# FlightControl.net
KiCad netlist of a schematic drawn in EAGLE
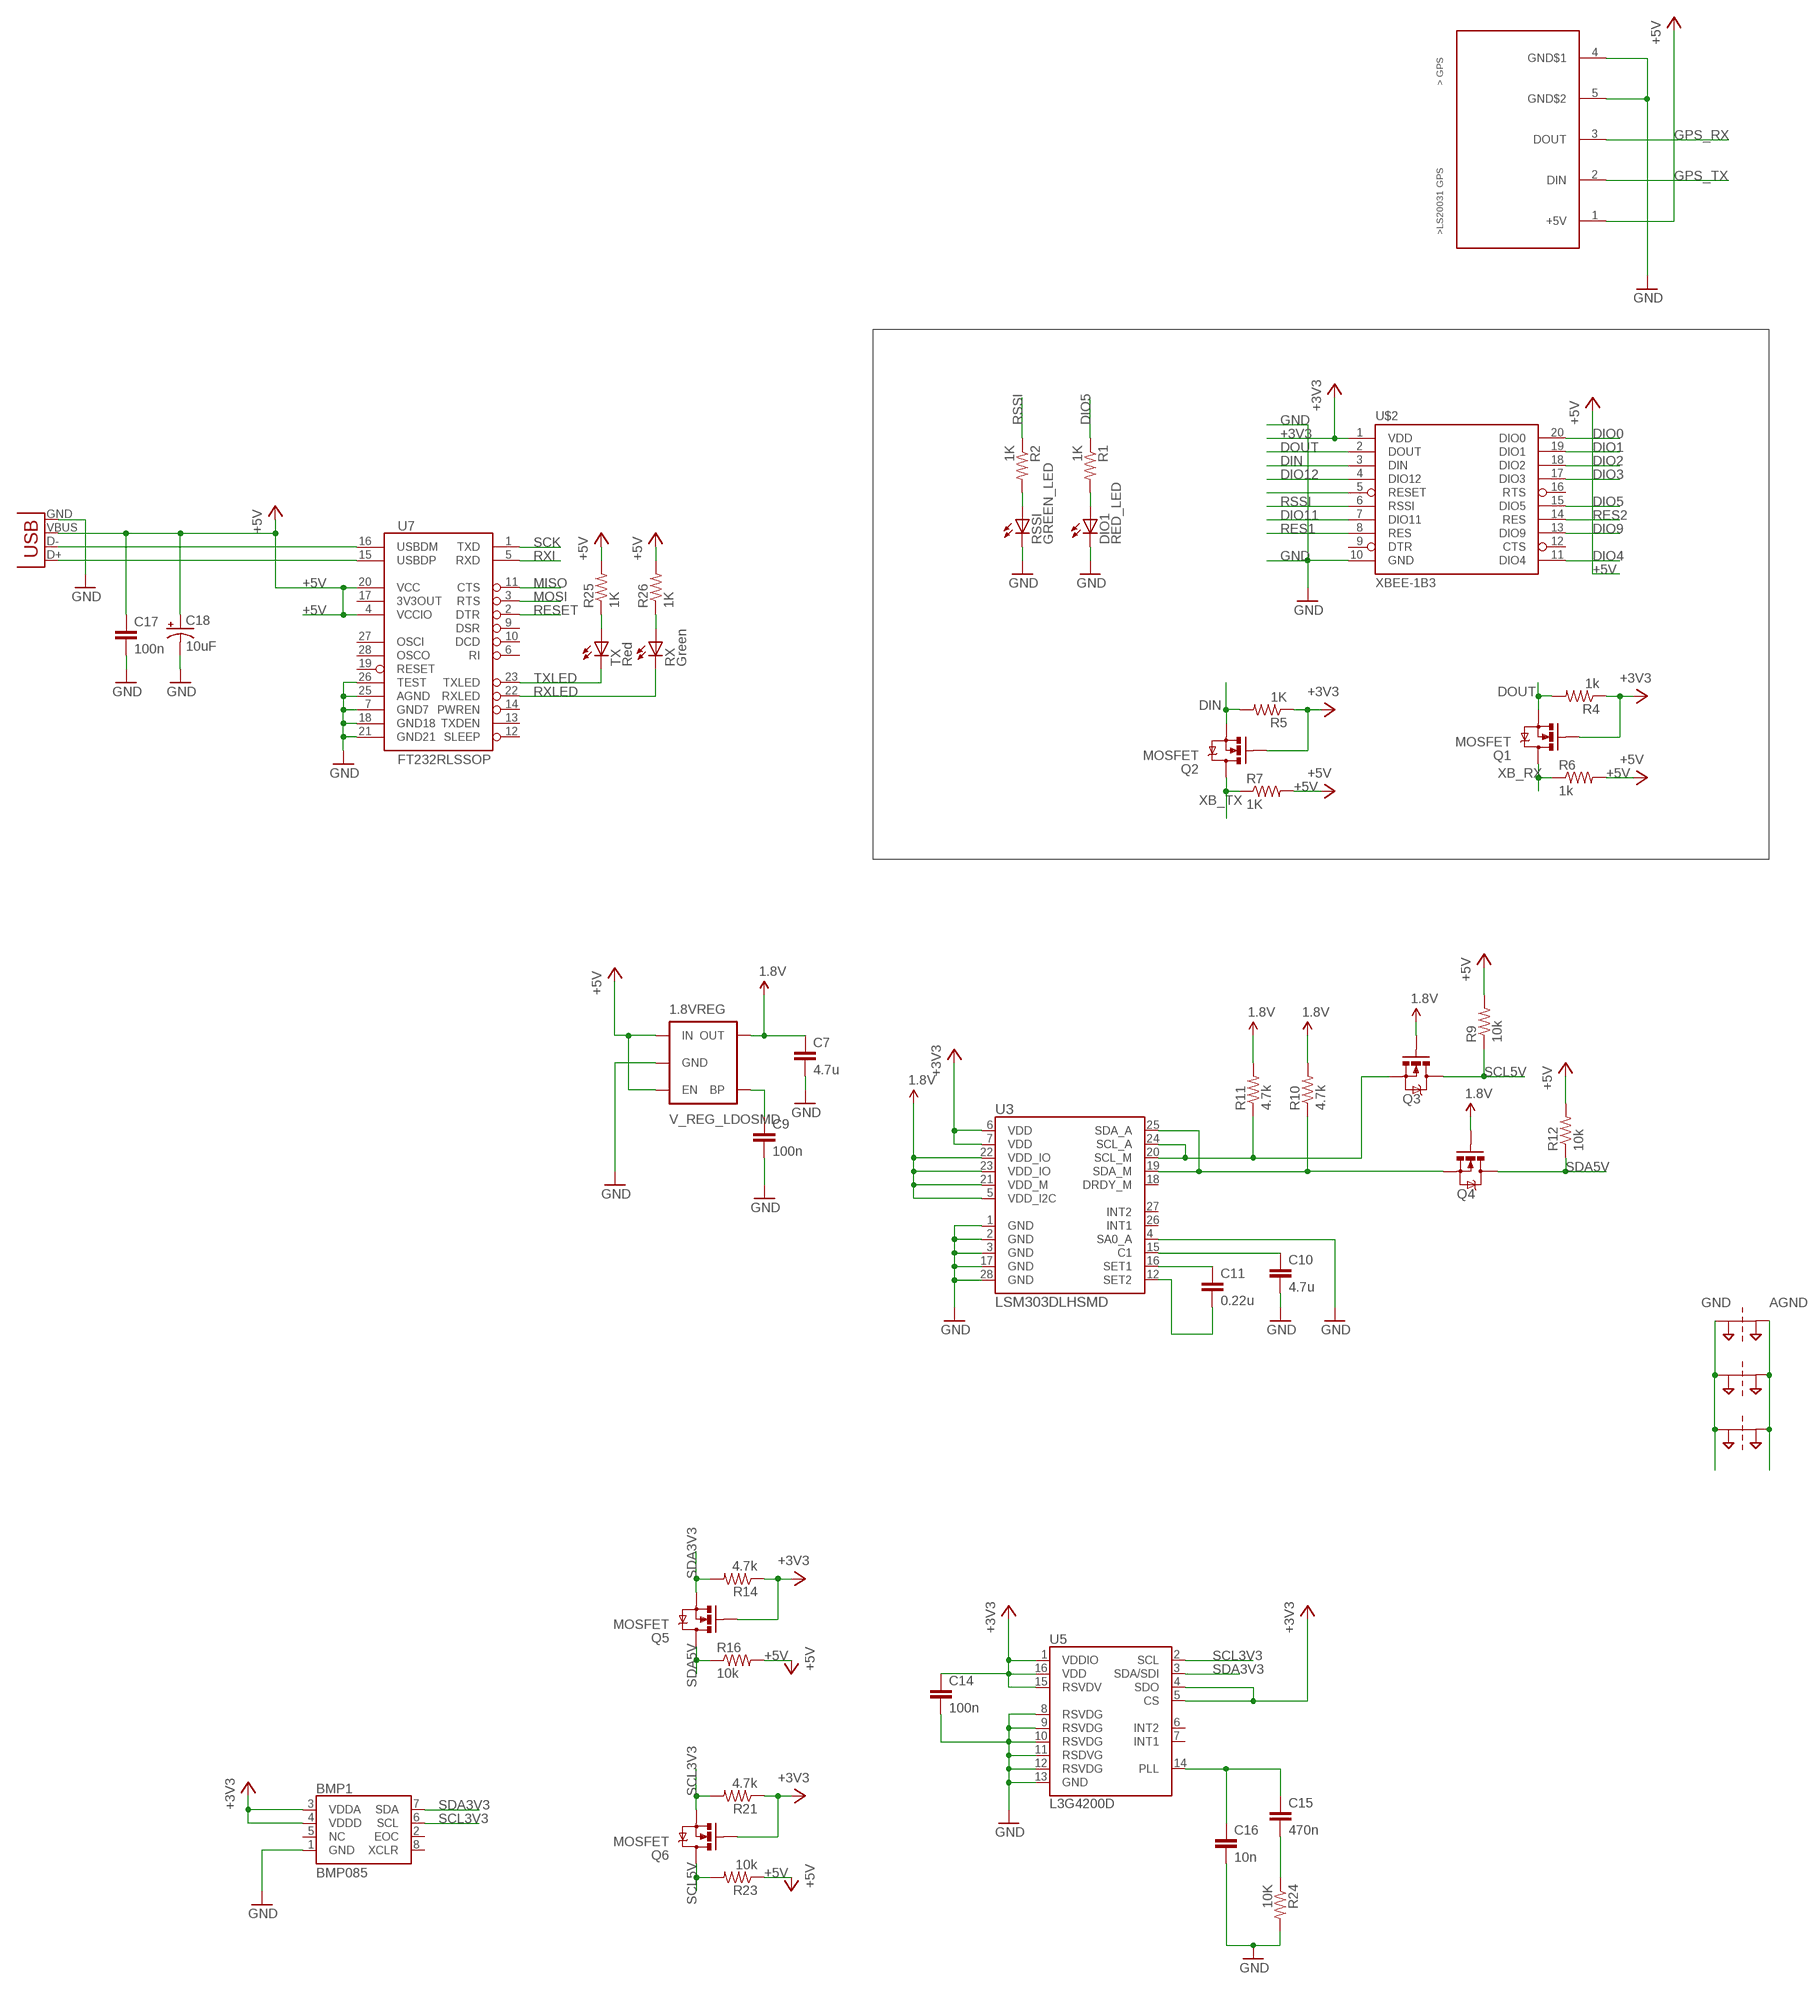
[diagram p0: schematic, sheet 1, part 1 of 2]
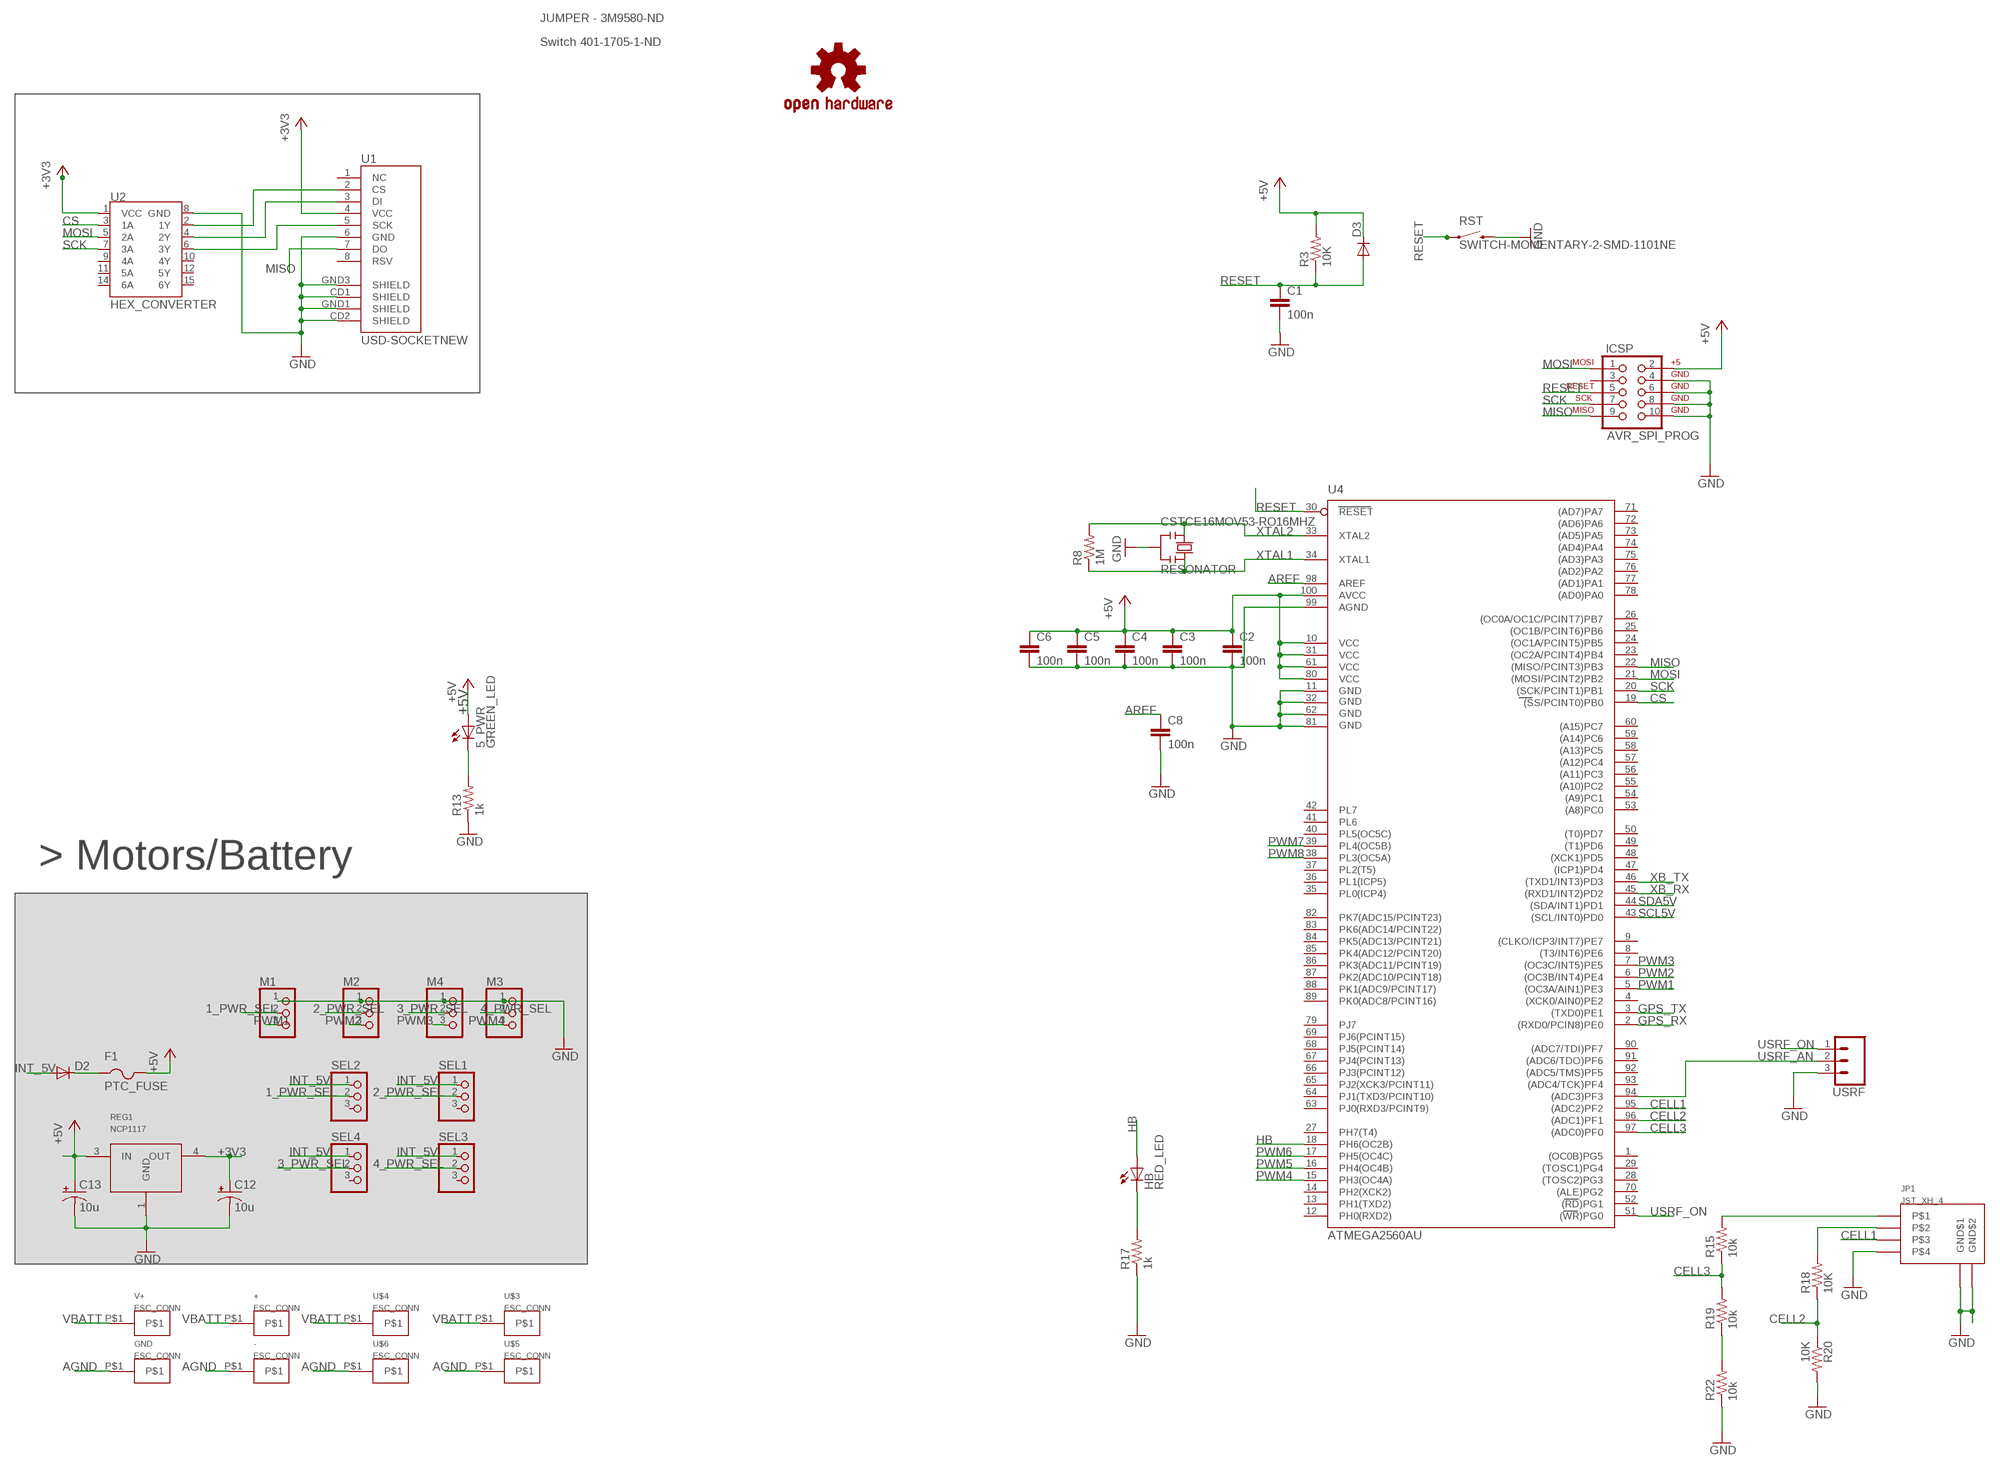
[diagram p1: schematic, sheet 1, part 2 of 2]

(export (version "E")
  (design (tool "Eeschema 10.0.6"))
  (components
    (comp (ref "+")
      (value "ESC_CONN")
      (footprint "eagle-import:ESC_CONN")
      (libsource (lib "eagle-import") (part "ESC_CONN"))
    )
    (comp (ref "-")
      (value "ESC_CONN")
      (footprint "eagle-import:ESC_CONN")
      (libsource (lib "eagle-import") (part "ESC_CONN"))
    )
    (comp (ref "1.8VREG")
      (value "V_REG_LDOSMD")
      (footprint "eagle-import:SOT23-5")
      (libsource (lib "eagle-import") (part "V_REG_LDOSMD"))
    )
    (comp (ref "5_PWR")
      (value "GREEN_LED")
      (footprint "eagle-import:LED-0603")
      (libsource (lib "eagle-import") (part "SparkFun-LED_LED0603"))
    )
    (comp (ref "BMP1")
      (value "BMP085")
      (footprint "eagle-import:BMP085")
      (libsource (lib "eagle-import") (part "BMP085"))
    )
    (comp (ref "C1")
      (value "100n")
      (footprint "eagle-import:0402-CAP")
      (libsource (lib "eagle-import") (part "SparkFun-Passives_CAP0402-CAP"))
    )
    (comp (ref "C2")
      (value "100n")
      (footprint "eagle-import:0402-CAP")
      (libsource (lib "eagle-import") (part "SparkFun-Passives_CAP0402-CAP"))
    )
    (comp (ref "C3")
      (value "100n")
      (footprint "eagle-import:0402-CAP")
      (libsource (lib "eagle-import") (part "SparkFun-Passives_CAP0402-CAP"))
    )
    (comp (ref "C4")
      (value "100n")
      (footprint "eagle-import:0402-CAP")
      (libsource (lib "eagle-import") (part "SparkFun-Passives_CAP0402-CAP"))
    )
    (comp (ref "C5")
      (value "100n")
      (footprint "eagle-import:0402-CAP")
      (libsource (lib "eagle-import") (part "SparkFun-Passives_CAP0402-CAP"))
    )
    (comp (ref "C6")
      (value "100n")
      (footprint "eagle-import:0402-CAP")
      (libsource (lib "eagle-import") (part "SparkFun-Passives_CAP0402-CAP"))
    )
    (comp (ref "C7")
      (value "4.7u")
      (footprint "eagle-import:0402-CAP")
      (libsource (lib "eagle-import") (part "SparkFun-Passives_CAP0402-CAP"))
    )
    (comp (ref "C8")
      (value "100n")
      (footprint "eagle-import:0402-CAP")
      (libsource (lib "eagle-import") (part "SparkFun-Passives_CAP0402-CAP"))
    )
    (comp (ref "C9")
      (value "100n")
      (footprint "eagle-import:0402-CAP")
      (libsource (lib "eagle-import") (part "SparkFun-Passives_CAP0402-CAP"))
    )
    (comp (ref "C10")
      (value "4.7u")
      (footprint "eagle-import:0402-CAP")
      (libsource (lib "eagle-import") (part "SparkFun-Passives_CAP0402-CAP"))
    )
    (comp (ref "C11")
      (value "0.22u")
      (footprint "eagle-import:0402-CAP")
      (libsource (lib "eagle-import") (part "SparkFun-Passives_CAP0402-CAP"))
    )
    (comp (ref "C12")
      (value "10u")
      (footprint "eagle-import:EIA3216")
      (libsource (lib "eagle-import") (part "SparkFun-Capacitors_CAP_POL1206"))
    )
    (comp (ref "C13")
      (value "10u")
      (footprint "eagle-import:EIA3216")
      (libsource (lib "eagle-import") (part "SparkFun-Capacitors_CAP_POL1206"))
    )
    (comp (ref "C14")
      (value "100n")
      (footprint "eagle-import:0402-CAP")
      (libsource (lib "eagle-import") (part "SparkFun-Capacitors_CAP0402-CAP"))
    )
    (comp (ref "C15")
      (value "470n")
      (footprint "eagle-import:0402-CAP")
      (libsource (lib "eagle-import") (part "SparkFun-Passives_CAP0402-CAP"))
    )
    (comp (ref "C16")
      (value "10n")
      (footprint "eagle-import:0402-CAP")
      (libsource (lib "eagle-import") (part "SparkFun-Passives_CAP0402-CAP"))
    )
    (comp (ref "C17")
      (value "100n")
      (footprint "eagle-import:0402-CAP")
      (libsource (lib "eagle-import") (part "CAP0402-CAP"))
    )
    (comp (ref "C18")
      (value "10uF")
      (footprint "eagle-import:EIA3216")
      (libsource (lib "eagle-import") (part "CAP_POL1206"))
    )
    (comp (ref "CSTCE16MOV53-RO16MHZ")
      (value "RESONATOR")
      (footprint "eagle-import:RESONATOR")
      (libsource (lib "eagle-import") (part "RESONATORMU"))
    )
    (comp (ref "D2")
      (value "SCHOTTKY-1206D1206")
      (footprint "eagle-import:C1206")
      (libsource (lib "eagle-import") (part "SCHOTTKY-1206D1206"))
    )
    (comp (ref "D3")
      (value "SCHOTTKY-1206D1206")
      (footprint "eagle-import:C1206")
      (libsource (lib "eagle-import") (part "SCHOTTKY-1206D1206"))
    )
    (comp (ref "DIO1")
      (value "RED_LED")
      (footprint "eagle-import:LED-0603")
      (libsource (lib "eagle-import") (part "SparkFun-LED_LED0603"))
    )
    (comp (ref "F1")
      (value "PTC_FUSE")
      (footprint "eagle-import:1812")
      (libsource (lib "eagle-import") (part "PTCFUSE-1812"))
    )
    (comp (ref "GND")
      (value "ESC_CONN")
      (footprint "eagle-import:ESC_CONN")
      (libsource (lib "eagle-import") (part "ESC_CONN"))
    )
    (comp (ref "HB")
      (value "RED_LED")
      (footprint "eagle-import:LED-0603")
      (libsource (lib "eagle-import") (part "SparkFun-LED_LED0603"))
    )
    (comp (ref "ICSP")
      (value "AVR_SPI_PROG")
      (footprint "eagle-import:AVR_ICSP")
      (libsource (lib "eagle-import") (part "AVR_SPI_PROG"))
    )
    (comp (ref "JP1")
      (value "JST_XH_4")
      (footprint "eagle-import:JST-XH4")
      (libsource (lib "eagle-import") (part "JST_XH_4"))
    )
    (comp (ref "LOGO1")
      (value "OSHW-LOGOL")
      (footprint "eagle-import:OSHW-LOGO-L")
      (libsource (lib "eagle-import") (part "OSHW-LOGOL"))
    )
    (comp (ref "M1")
      (value "PINHD-1X3")
      (footprint "eagle-import:1X03")
      (libsource (lib "eagle-import") (part "PINHD-1X3"))
    )
    (comp (ref "M2")
      (value "PINHD-1X3")
      (footprint "eagle-import:1X03")
      (libsource (lib "eagle-import") (part "PINHD-1X3"))
    )
    (comp (ref "M3")
      (value "PINHD-1X3")
      (footprint "eagle-import:1X03")
      (libsource (lib "eagle-import") (part "PINHD-1X3"))
    )
    (comp (ref "M4")
      (value "PINHD-1X3")
      (footprint "eagle-import:1X03")
      (libsource (lib "eagle-import") (part "PINHD-1X3"))
    )
    (comp (ref "PT1")
      (value "2PT_GND_TIE")
      (footprint "eagle-import:2PT_GND_TIE")
      (libsource (lib "eagle-import") (part "2PT_GND_TIE"))
    )
    (comp (ref "PT2")
      (value "2PT_GND_TIE")
      (footprint "eagle-import:2PT_GND_TIE")
      (libsource (lib "eagle-import") (part "2PT_GND_TIE"))
    )
    (comp (ref "PT3")
      (value "2PT_GND_TIE")
      (footprint "eagle-import:2PT_GND_TIE")
      (libsource (lib "eagle-import") (part "2PT_GND_TIE"))
    )
    (comp (ref "Q1")
      (value "MOSFET")
      (footprint "eagle-import:SOT23")
      (libsource (lib "eagle-import") (part "MOSFET-NCHANNELBSS138"))
    )
    (comp (ref "Q2")
      (value "MOSFET")
      (footprint "eagle-import:SOT23")
      (libsource (lib "eagle-import") (part "MOSFET-NCHANNELBSS138"))
    )
    (comp (ref "Q3")
      (value "MOSFET")
      (footprint "eagle-import:SOT23")
      (libsource (lib "eagle-import") (part "MOSFET-NCHANNELBSS138"))
    )
    (comp (ref "Q4")
      (value "MOSFET")
      (footprint "eagle-import:SOT23")
      (libsource (lib "eagle-import") (part "MOSFET-NCHANNELBSS138"))
    )
    (comp (ref "Q5")
      (value "MOSFET")
      (footprint "eagle-import:SOT23")
      (libsource (lib "eagle-import") (part "MOSFET-NCHANNELBSS138"))
    )
    (comp (ref "Q6")
      (value "MOSFET")
      (footprint "eagle-import:SOT23")
      (libsource (lib "eagle-import") (part "MOSFET-NCHANNELBSS138"))
    )
    (comp (ref "R1")
      (value "1K")
      (footprint "eagle-import:0603-RES")
      (libsource (lib "eagle-import") (part "RESISTOR0603-RES"))
    )
    (comp (ref "R2")
      (value "1K")
      (footprint "eagle-import:0603-RES")
      (libsource (lib "eagle-import") (part "RESISTOR0603-RES"))
    )
    (comp (ref "R3")
      (value "10K")
      (footprint "eagle-import:0603-RES")
      (libsource (lib "eagle-import") (part "RESISTOR0603-RES"))
    )
    (comp (ref "R4")
      (value "1k")
      (footprint "eagle-import:0603-RES")
      (libsource (lib "eagle-import") (part "RESISTOR0603-RES"))
    )
    (comp (ref "R5")
      (value "1K")
      (footprint "eagle-import:0603-RES")
      (libsource (lib "eagle-import") (part "RESISTOR0603-RES"))
    )
    (comp (ref "R6")
      (value "1k")
      (footprint "eagle-import:0603-RES")
      (libsource (lib "eagle-import") (part "RESISTOR0603-RES"))
    )
    (comp (ref "R7")
      (value "1K")
      (footprint "eagle-import:0603-RES")
      (libsource (lib "eagle-import") (part "RESISTOR0603-RES"))
    )
    (comp (ref "R8")
      (value "1M")
      (footprint "eagle-import:0603-RES")
      (libsource (lib "eagle-import") (part "RESISTOR0603-RES"))
    )
    (comp (ref "R9")
      (value "10k")
      (footprint "eagle-import:0603-RES")
      (libsource (lib "eagle-import") (part "RESISTOR0603-RES"))
    )
    (comp (ref "R10")
      (value "4.7k")
      (footprint "eagle-import:0402-RES")
      (libsource (lib "eagle-import") (part "RESISTOR0402-RES"))
    )
    (comp (ref "R11")
      (value "4.7k")
      (footprint "eagle-import:0603-RES")
      (libsource (lib "eagle-import") (part "RESISTOR0603-RES"))
    )
    (comp (ref "R12")
      (value "10k")
      (footprint "eagle-import:0603-RES")
      (libsource (lib "eagle-import") (part "RESISTOR0603-RES"))
    )
    (comp (ref "R13")
      (value "1k")
      (footprint "eagle-import:0603-RES")
      (libsource (lib "eagle-import") (part "RESISTOR0603-RES"))
    )
    (comp (ref "R14")
      (value "4.7k")
      (footprint "eagle-import:0603-RES")
      (libsource (lib "eagle-import") (part "RESISTOR0603-RES"))
    )
    (comp (ref "R15")
      (value "10k")
      (footprint "eagle-import:0603-RES")
      (libsource (lib "eagle-import") (part "RESISTOR0603-RES"))
    )
    (comp (ref "R16")
      (value "10k")
      (footprint "eagle-import:0603-RES")
      (libsource (lib "eagle-import") (part "RESISTOR0603-RES"))
    )
    (comp (ref "R17")
      (value "1k")
      (footprint "eagle-import:0603-RES")
      (libsource (lib "eagle-import") (part "RESISTOR0603-RES"))
    )
    (comp (ref "R18")
      (value "10K")
      (footprint "eagle-import:0603-RES")
      (libsource (lib "eagle-import") (part "RESISTOR0603-RES"))
    )
    (comp (ref "R19")
      (value "10k")
      (footprint "eagle-import:0603-RES")
      (libsource (lib "eagle-import") (part "RESISTOR0603-RES"))
    )
    (comp (ref "R20")
      (value "10K")
      (footprint "eagle-import:0603-RES")
      (libsource (lib "eagle-import") (part "RESISTOR0603-RES"))
    )
    (comp (ref "R21")
      (value "4.7k")
      (footprint "eagle-import:0603-RES")
      (libsource (lib "eagle-import") (part "RESISTOR0603-RES"))
    )
    (comp (ref "R22")
      (value "10k")
      (footprint "eagle-import:0603-RES")
      (libsource (lib "eagle-import") (part "RESISTOR0603-RES"))
    )
    (comp (ref "R23")
      (value "10k")
      (footprint "eagle-import:0603-RES")
      (libsource (lib "eagle-import") (part "RESISTOR0603-RES"))
    )
    (comp (ref "R24")
      (value "10K")
      (footprint "eagle-import:0603-RES")
      (libsource (lib "eagle-import") (part "RESISTOR0603-RES"))
    )
    (comp (ref "R25")
      (value "1K")
      (footprint "eagle-import:0603-RES")
      (libsource (lib "eagle-import") (part "RESISTOR0603-RES"))
    )
    (comp (ref "R26")
      (value "1K")
      (footprint "eagle-import:0603-RES")
      (libsource (lib "eagle-import") (part "RESISTOR0603-RES"))
    )
    (comp (ref "REG1")
      (value "NCP1117")
      (footprint "eagle-import:DPAK")
      (libsource (lib "eagle-import") (part "NCP1117"))
    )
    (comp (ref "RSSI")
      (value "GREEN_LED")
      (footprint "eagle-import:LED-0603")
      (libsource (lib "eagle-import") (part "SparkFun-LED_LED0603"))
    )
    (comp (ref "RST")
      (value "SWITCH-MOMENTARY-2-SMD-1101NE")
      (footprint "eagle-import:TACTILE-SWITCH-1101NE")
      (libsource (lib "eagle-import") (part "SWITCH-MOMENTARY-2-SMD-1101NE"))
    )
    (comp (ref "RX")
      (value "Green")
      (footprint "eagle-import:LED-0603")
      (libsource (lib "eagle-import") (part "LED0603"))
    )
    (comp (ref "SEL1")
      (value "PINHD-1X3")
      (footprint "eagle-import:1X03")
      (libsource (lib "eagle-import") (part "PINHD-1X3"))
    )
    (comp (ref "SEL2")
      (value "PINHD-1X3")
      (footprint "eagle-import:1X03")
      (libsource (lib "eagle-import") (part "PINHD-1X3"))
    )
    (comp (ref "SEL3")
      (value "PINHD-1X3")
      (footprint "eagle-import:1X03")
      (libsource (lib "eagle-import") (part "PINHD-1X3"))
    )
    (comp (ref "SEL4")
      (value "PINHD-1X3")
      (footprint "eagle-import:1X03")
      (libsource (lib "eagle-import") (part "PINHD-1X3"))
    )
    (comp (ref "TX")
      (value "Red")
      (footprint "eagle-import:LED-0603")
      (libsource (lib "eagle-import") (part "LED0603"))
    )
    (comp (ref "U$1")
      (value "LS20031")
      (footprint "eagle-import:LS20031")
      (libsource (lib "eagle-import") (part "LS20031"))
    )
    (comp (ref "U$2")
      (value "XBEE-1B3")
      (footprint "eagle-import:XBEE-SMD")
      (libsource (lib "eagle-import") (part "XBEE-1B3"))
    )
    (comp (ref "U$3")
      (value "ESC_CONN")
      (footprint "eagle-import:ESC_CONN")
      (libsource (lib "eagle-import") (part "ESC_CONN"))
    )
    (comp (ref "U$4")
      (value "ESC_CONN")
      (footprint "eagle-import:ESC_CONN")
      (libsource (lib "eagle-import") (part "ESC_CONN"))
    )
    (comp (ref "U$5")
      (value "ESC_CONN")
      (footprint "eagle-import:ESC_CONN")
      (libsource (lib "eagle-import") (part "ESC_CONN"))
    )
    (comp (ref "U$6")
      (value "ESC_CONN")
      (footprint "eagle-import:ESC_CONN")
      (libsource (lib "eagle-import") (part "ESC_CONN"))
    )
    (comp (ref "U1")
      (value "USD-SOCKETNEW")
      (footprint "eagle-import:MICRO-SD-SOCKET-PP")
      (libsource (lib "eagle-import") (part "USD-SOCKETNEW"))
    )
    (comp (ref "U2")
      (value "HEX_CONVERTER")
      (footprint "eagle-import:SO016")
      (libsource (lib "eagle-import") (part "HEX_CONVERTER"))
    )
    (comp (ref "U3")
      (value "LSM303DLHSMD")
      (footprint "eagle-import:LGA28-5X5")
      (libsource (lib "eagle-import") (part "LSM303DLHSMD"))
    )
    (comp (ref "U4")
      (value "ATMEGA2560AU")
      (footprint "eagle-import:TQFP100")
      (libsource (lib "eagle-import") (part "ATMEGA2560AU"))
    )
    (comp (ref "U5")
      (value "L3G4200D")
      (footprint "eagle-import:LGA16-4X4")
      (libsource (lib "eagle-import") (part "L3G4200D"))
    )
    (comp (ref "U7")
      (value "FT232RLSSOP")
      (footprint "eagle-import:SSOP28DB")
      (libsource (lib "eagle-import") (part "FT232RLSSOP"))
    )
    (comp (ref "USRF")
      (value "M03LOCK")
      (footprint "eagle-import:1X03_LOCK")
      (libsource (lib "eagle-import") (part "M03LOCK"))
    )
    (comp (ref "V+")
      (value "ESC_CONN")
      (footprint "eagle-import:ESC_CONN")
      (libsource (lib "eagle-import") (part "ESC_CONN"))
    )
    (comp (ref "X2")
      (value "USB-SMD-NS")
      (footprint "eagle-import:USB-MINIB-NOSTOP")
      (libsource (lib "eagle-import") (part "USB-SMD-NS"))
    )
  )
  (nets
    (net (code "1") (name "+3V3") (class "Default")
      (node (ref "BMP1") (pin "3") (pinfunction "VDDA_3") (pintype "power_in"))
      (node (ref "BMP1") (pin "4") (pinfunction "VDDD_4") (pintype "power_in"))
      (node (ref "C12") (pin "A") (pinfunction "+_A") (pintype "passive"))
      (node (ref "C14") (pin "1") (pinfunction "1_1") (pintype "passive"))
      (node (ref "Q1") (pin "1") (pinfunction "G_1") (pintype "passive"))
      (node (ref "Q2") (pin "1") (pinfunction "G_1") (pintype "passive"))
      (node (ref "Q5") (pin "1") (pinfunction "G_1") (pintype "passive"))
      (node (ref "Q6") (pin "1") (pinfunction "G_1") (pintype "passive"))
      (node (ref "R14") (pin "1") (pinfunction "1_1") (pintype "passive"))
      (node (ref "R21") (pin "1") (pinfunction "1_1") (pintype "passive"))
      (node (ref "R4") (pin "1") (pinfunction "1_1") (pintype "passive"))
      (node (ref "R5") (pin "1") (pinfunction "1_1") (pintype "passive"))
      (node (ref "REG1") (pin "4") (pinfunction "OUT_4") (pintype "bidirectional"))
      (node (ref "U$2") (pin "1") (pinfunction "VDD_1") (pintype "power_in"))
      (node (ref "U1") (pin "4") (pinfunction "VCC_4") (pintype "bidirectional"))
      (node (ref "U2") (pin "1") (pinfunction "VCC_1") (pintype "bidirectional"))
      (node (ref "U3") (pin "6") (pinfunction "VDD_6") (pintype "bidirectional"))
      (node (ref "U3") (pin "7") (pinfunction "VDD_7") (pintype "bidirectional"))
      (node (ref "U5") (pin "1") (pinfunction "VDDIO_1") (pintype "bidirectional"))
      (node (ref "U5") (pin "15") (pinfunction "RSVDV_15") (pintype "bidirectional"))
      (node (ref "U5") (pin "16") (pinfunction "VDD_16") (pintype "bidirectional"))
      (node (ref "U5") (pin "4") (pinfunction "SDO_4") (pintype "bidirectional"))
      (node (ref "U5") (pin "5") (pinfunction "CS_5") (pintype "bidirectional"))
    )
    (net (code "2") (name "+5V") (class "Default")
      (node (ref "1.8VREG") (pin "1") (pinfunction "IN_1") (pintype "input"))
      (node (ref "1.8VREG") (pin "3") (pinfunction "EN_3") (pintype "input"))
      (node (ref "5_PWR") (pin "A") (pinfunction "A_A") (pintype "passive"))
      (node (ref "C13") (pin "A") (pinfunction "+_A") (pintype "passive"))
      (node (ref "C17") (pin "1") (pinfunction "1_1") (pintype "passive"))
      (node (ref "C18") (pin "A") (pinfunction "+_A") (pintype "passive"))
      (node (ref "C2") (pin "1") (pinfunction "1_1") (pintype "passive"))
      (node (ref "C3") (pin "1") (pinfunction "1_1") (pintype "passive"))
      (node (ref "C4") (pin "1") (pinfunction "1_1") (pintype "passive"))
      (node (ref "C5") (pin "1") (pinfunction "1_1") (pintype "passive"))
      (node (ref "C6") (pin "1") (pinfunction "1_1") (pintype "passive"))
      (node (ref "D3") (pin "2") (pinfunction "C_2") (pintype "passive"))
      (node (ref "F1") (pin "2") (pinfunction "2_2") (pintype "passive"))
      (node (ref "ICSP") (pin "2") (pinfunction "2_2") (pintype "passive"))
      (node (ref "R12") (pin "2") (pinfunction "2_2") (pintype "passive"))
      (node (ref "R16") (pin "2") (pinfunction "2_2") (pintype "passive"))
      (node (ref "R23") (pin "1") (pinfunction "1_1") (pintype "passive"))
      (node (ref "R25") (pin "2") (pinfunction "2_2") (pintype "passive"))
      (node (ref "R26") (pin "2") (pinfunction "2_2") (pintype "passive"))
      (node (ref "R3") (pin "2") (pinfunction "2_2") (pintype "passive"))
      (node (ref "R6") (pin "2") (pinfunction "2_2") (pintype "passive"))
      (node (ref "R7") (pin "2") (pinfunction "2_2") (pintype "passive"))
      (node (ref "R9") (pin "2") (pinfunction "2_2") (pintype "passive"))
      (node (ref "REG1") (pin "3") (pinfunction "IN_3") (pintype "bidirectional"))
      (node (ref "U$1") (pin "1") (pinfunction "+5V_1") (pintype "bidirectional"))
      (node (ref "U4") (pin "10") (pinfunction "VCC_10") (pintype "power_in"))
      (node (ref "U4") (pin "100") (pinfunction "AVCC_100") (pintype "power_in"))
      (node (ref "U4") (pin "31") (pinfunction "VCC1_31") (pintype "power_in"))
      (node (ref "U4") (pin "61") (pinfunction "VCC2_61") (pintype "power_in"))
      (node (ref "U4") (pin "80") (pinfunction "VCC3_80") (pintype "power_in"))
      (node (ref "U7") (pin "20") (pinfunction "VCC_20") (pintype "power_in"))
      (node (ref "U7") (pin "4") (pinfunction "VCCIO_4") (pintype "power_in"))
      (node (ref "X2") (pin "VBUS") (pinfunction "VBUS_VBUS") (pintype "bidirectional"))
    )
    (net (code "3") (name "/1_PWR_SEL") (class "Default")
      (node (ref "M1") (pin "2") (pinfunction "2_2") (pintype "passive"))
      (node (ref "SEL2") (pin "2") (pinfunction "2_2") (pintype "passive"))
    )
    (net (code "4") (name "/2_PWR_SEL") (class "Default")
      (node (ref "M2") (pin "2") (pinfunction "2_2") (pintype "passive"))
      (node (ref "SEL1") (pin "2") (pinfunction "2_2") (pintype "passive"))
    )
    (net (code "5") (name "/3_PWR_SEL") (class "Default")
      (node (ref "M4") (pin "2") (pinfunction "2_2") (pintype "passive"))
      (node (ref "SEL4") (pin "2") (pinfunction "2_2") (pintype "passive"))
    )
    (net (code "6") (name "/4_PWR_SEL") (class "Default")
      (node (ref "M3") (pin "2") (pinfunction "2_2") (pintype "passive"))
      (node (ref "SEL3") (pin "2") (pinfunction "2_2") (pintype "passive"))
    )
    (net (code "7") (name "/AGND") (class "Default")
      (node (ref "-") (pin "P$1") (pinfunction "P$1_P$1") (pintype "bidirectional"))
      (node (ref "GND") (pin "P$1") (pinfunction "P$1_P$1") (pintype "bidirectional"))
      (node (ref "PT1") (pin "P$2") (pinfunction "P$2_P$2") (pintype "bidirectional"))
      (node (ref "PT2") (pin "P$2") (pinfunction "P$2_P$2") (pintype "bidirectional"))
      (node (ref "PT3") (pin "P$2") (pinfunction "P$2_P$2") (pintype "bidirectional"))
      (node (ref "U$5") (pin "P$1") (pinfunction "P$1_P$1") (pintype "bidirectional"))
      (node (ref "U$6") (pin "P$1") (pinfunction "P$1_P$1") (pintype "bidirectional"))
    )
    (net (code "8") (name "/AREF") (class "Default")
      (node (ref "C8") (pin "1") (pinfunction "1_1") (pintype "passive"))
      (node (ref "U4") (pin "98") (pinfunction "AREF_98") (pintype "bidirectional"))
    )
    (net (code "9") (name "/CELL1") (class "Default")
      (node (ref "JP1") (pin "P$3") (pinfunction "P$3_P$3") (pintype "bidirectional"))
      (node (ref "U4") (pin "95") (pinfunction "(ADC2)PF2_95") (pintype "bidirectional"))
    )
    (net (code "10") (name "/CELL2") (class "Default")
      (node (ref "R18") (pin "1") (pinfunction "1_1") (pintype "passive"))
      (node (ref "R20") (pin "1") (pinfunction "1_1") (pintype "passive"))
      (node (ref "U4") (pin "96") (pinfunction "(ADC1)PF1_96") (pintype "bidirectional"))
    )
    (net (code "11") (name "/CELL3") (class "Default")
      (node (ref "R15") (pin "1") (pinfunction "1_1") (pintype "passive"))
      (node (ref "R19") (pin "2") (pinfunction "2_2") (pintype "passive"))
      (node (ref "U4") (pin "97") (pinfunction "(ADC0)PF0_97") (pintype "bidirectional"))
    )
    (net (code "12") (name "/CS") (class "Default")
      (node (ref "U2") (pin "3") (pinfunction "1A_3") (pintype "bidirectional"))
      (node (ref "U4") (pin "19") (pinfunction "(SS/PCINT0)PB0_19") (pintype "bidirectional"))
    )
    (net (code "13") (name "/DIN") (class "Default")
      (node (ref "Q2") (pin "2") (pinfunction "S_2") (pintype "passive"))
      (node (ref "R5") (pin "2") (pinfunction "2_2") (pintype "passive"))
      (node (ref "U$2") (pin "3") (pinfunction "DIN_3") (pintype "input"))
    )
    (net (code "14") (name "/DIO0") (class "Default")
      (node (ref "U$2") (pin "20") (pinfunction "DIO0_20") (pintype "bidirectional"))
    )
    (net (code "15") (name "/DIO1") (class "Default")
      (node (ref "U$2") (pin "19") (pinfunction "DIO1_19") (pintype "bidirectional"))
    )
    (net (code "16") (name "/DIO2") (class "Default")
      (node (ref "U$2") (pin "18") (pinfunction "DIO2_18") (pintype "bidirectional"))
    )
    (net (code "17") (name "/DIO3") (class "Default")
      (node (ref "U$2") (pin "17") (pinfunction "DIO3_17") (pintype "bidirectional"))
    )
    (net (code "18") (name "/DIO4") (class "Default")
      (node (ref "U$2") (pin "11") (pinfunction "DIO4_11") (pintype "bidirectional"))
    )
    (net (code "19") (name "/DIO5") (class "Default")
      (node (ref "R1") (pin "1") (pinfunction "1_1") (pintype "passive"))
      (node (ref "U$2") (pin "15") (pinfunction "DIO5_15") (pintype "bidirectional"))
    )
    (net (code "20") (name "/DIO9") (class "Default")
      (node (ref "U$2") (pin "13") (pinfunction "DIO9_13") (pintype "bidirectional"))
    )
    (net (code "21") (name "/DIO11") (class "Default")
      (node (ref "U$2") (pin "7") (pinfunction "DIO11_7") (pintype "bidirectional"))
    )
    (net (code "22") (name "/DIO12") (class "Default")
      (node (ref "U$2") (pin "4") (pinfunction "DIO12_4") (pintype "bidirectional"))
    )
    (net (code "23") (name "/DOUT") (class "Default")
      (node (ref "Q1") (pin "2") (pinfunction "S_2") (pintype "passive"))
      (node (ref "R4") (pin "2") (pinfunction "2_2") (pintype "passive"))
      (node (ref "U$2") (pin "2") (pinfunction "DOUT_2") (pintype "output"))
    )
    (net (code "24") (name "/GPS_RX") (class "Default")
      (node (ref "U$1") (pin "3") (pinfunction "DOUT_3") (pintype "output"))
      (node (ref "U4") (pin "2") (pinfunction "(RXD0/PCIN8)PE0_2") (pintype "bidirectional"))
    )
    (net (code "25") (name "/GPS_TX") (class "Default")
      (node (ref "U$1") (pin "2") (pinfunction "DIN_2") (pintype "bidirectional"))
      (node (ref "U4") (pin "3") (pinfunction "(TXD0)PE1_3") (pintype "bidirectional"))
    )
    (net (code "26") (name "/HB") (class "Default")
      (node (ref "HB") (pin "A") (pinfunction "A_A") (pintype "passive"))
      (node (ref "U4") (pin "18") (pinfunction "PH6(OC2B)_18") (pintype "bidirectional"))
    )
    (net (code "27") (name "/INT_5V") (class "Default")
      (node (ref "D2") (pin "1") (pinfunction "A_1") (pintype "passive"))
      (node (ref "SEL1") (pin "1") (pinfunction "1_1") (pintype "passive"))
      (node (ref "SEL2") (pin "1") (pinfunction "1_1") (pintype "passive"))
      (node (ref "SEL3") (pin "1") (pinfunction "1_1") (pintype "passive"))
      (node (ref "SEL4") (pin "1") (pinfunction "1_1") (pintype "passive"))
    )
    (net (code "28") (name "/MISO") (class "Default")
      (node (ref "ICSP") (pin "9") (pinfunction "9_9") (pintype "passive"))
      (node (ref "U1") (pin "7") (pinfunction "DO_7") (pintype "bidirectional"))
      (node (ref "U4") (pin "22") (pinfunction "(MISO/PCINT3)PB3_22") (pintype "bidirectional"))
      (node (ref "U7") (pin "11") (pinfunction "CTS_11") (pintype "input"))
    )
    (net (code "29") (name "/MOSI") (class "Default")
      (node (ref "ICSP") (pin "1") (pinfunction "1_1") (pintype "passive"))
      (node (ref "U2") (pin "5") (pinfunction "2A_5") (pintype "bidirectional"))
      (node (ref "U4") (pin "21") (pinfunction "(MOSI/PCINT2)PB2_21") (pintype "bidirectional"))
      (node (ref "U7") (pin "3") (pinfunction "RTS_3") (pintype "output"))
    )
    (net (code "30") (name "/PWM1") (class "Default")
      (node (ref "M1") (pin "3") (pinfunction "3_3") (pintype "passive"))
      (node (ref "U4") (pin "5") (pinfunction "(OC3A/AIN1)PE3_5") (pintype "bidirectional"))
    )
    (net (code "31") (name "/PWM2") (class "Default")
      (node (ref "M2") (pin "3") (pinfunction "3_3") (pintype "passive"))
      (node (ref "U4") (pin "6") (pinfunction "(OC3B/INT4)PE4_6") (pintype "bidirectional"))
    )
    (net (code "32") (name "/PWM3") (class "Default")
      (node (ref "M4") (pin "3") (pinfunction "3_3") (pintype "passive"))
      (node (ref "U4") (pin "7") (pinfunction "(OC3C/INT5)PE5_7") (pintype "bidirectional"))
    )
    (net (code "33") (name "/PWM4") (class "Default")
      (node (ref "M3") (pin "3") (pinfunction "3_3") (pintype "passive"))
      (node (ref "U4") (pin "15") (pinfunction "PH3(OC4A)_15") (pintype "bidirectional"))
    )
    (net (code "34") (name "/PWM5") (class "Default")
      (node (ref "U4") (pin "16") (pinfunction "PH4(OC4B)_16") (pintype "bidirectional"))
    )
    (net (code "35") (name "/PWM6") (class "Default")
      (node (ref "U4") (pin "17") (pinfunction "PH5(OC4C)_17") (pintype "bidirectional"))
    )
    (net (code "36") (name "/PWM7") (class "Default")
      (node (ref "U4") (pin "39") (pinfunction "PL4(OC5B)_39") (pintype "bidirectional"))
    )
    (net (code "37") (name "/PWM8") (class "Default")
      (node (ref "U4") (pin "38") (pinfunction "PL3(OC5A)_38") (pintype "bidirectional"))
    )
    (net (code "38") (name "/RES1") (class "Default")
      (node (ref "U$2") (pin "8") (pinfunction "RES_8") (pintype "bidirectional"))
    )
    (net (code "39") (name "/RES2") (class "Default")
      (node (ref "U$2") (pin "14") (pinfunction "RES_14") (pintype "bidirectional"))
    )
    (net (code "40") (name "/RESET") (class "Default")
      (node (ref "C1") (pin "1") (pinfunction "1_1") (pintype "passive"))
      (node (ref "D3") (pin "1") (pinfunction "A_1") (pintype "passive"))
      (node (ref "ICSP") (pin "5") (pinfunction "5_5") (pintype "passive"))
      (node (ref "R3") (pin "1") (pinfunction "1_1") (pintype "passive"))
      (node (ref "RST") (pin "P$1") (pinfunction "1_P$1") (pintype "passive"))
      (node (ref "U4") (pin "30") (pinfunction "RESET_30") (pintype "input"))
      (node (ref "U7") (pin "2") (pinfunction "DTR_2") (pintype "output"))
    )
    (net (code "41") (name "/RSSI") (class "Default")
      (node (ref "R2") (pin "1") (pinfunction "1_1") (pintype "passive"))
      (node (ref "U$2") (pin "6") (pinfunction "RSSI_6") (pintype "bidirectional"))
    )
    (net (code "42") (name "/RXI") (class "Default")
      (node (ref "U7") (pin "5") (pinfunction "RXD_5") (pintype "input"))
    )
    (net (code "43") (name "/RXLED") (class "Default")
      (node (ref "RX") (pin "C") (pinfunction "C_C") (pintype "passive"))
      (node (ref "U7") (pin "22") (pinfunction "RXLED_22") (pintype "input"))
    )
    (net (code "44") (name "/SCK") (class "Default")
      (node (ref "ICSP") (pin "7") (pinfunction "7_7") (pintype "passive"))
      (node (ref "U2") (pin "7") (pinfunction "3A_7") (pintype "bidirectional"))
      (node (ref "U4") (pin "20") (pinfunction "(SCK/PCINT1)PB1_20") (pintype "bidirectional"))
      (node (ref "U7") (pin "1") (pinfunction "TXD_1") (pintype "output"))
    )
    (net (code "45") (name "/SCL3V3") (class "Default")
      (node (ref "BMP1") (pin "6") (pinfunction "SCL_6") (pintype "input"))
      (node (ref "Q6") (pin "2") (pinfunction "S_2") (pintype "passive"))
      (node (ref "R21") (pin "2") (pinfunction "2_2") (pintype "passive"))
      (node (ref "U5") (pin "2") (pinfunction "SCL_2") (pintype "bidirectional"))
    )
    (net (code "46") (name "/SCL5V") (class "Default")
      (node (ref "Q3") (pin "3") (pinfunction "D_3") (pintype "passive"))
      (node (ref "Q6") (pin "3") (pinfunction "D_3") (pintype "passive"))
      (node (ref "R23") (pin "2") (pinfunction "2_2") (pintype "passive"))
      (node (ref "R9") (pin "1") (pinfunction "1_1") (pintype "passive"))
      (node (ref "U4") (pin "43") (pinfunction "(SCL/INT0)PD0_43") (pintype "bidirectional"))
    )
    (net (code "47") (name "/SDA3V3") (class "Default")
      (node (ref "BMP1") (pin "7") (pinfunction "SDA_7") (pintype "bidirectional"))
      (node (ref "Q5") (pin "2") (pinfunction "S_2") (pintype "passive"))
      (node (ref "R14") (pin "2") (pinfunction "2_2") (pintype "passive"))
      (node (ref "U5") (pin "3") (pinfunction "SDA/SDI_3") (pintype "bidirectional"))
    )
    (net (code "48") (name "/SDA5V") (class "Default")
      (node (ref "Q4") (pin "3") (pinfunction "D_3") (pintype "passive"))
      (node (ref "Q5") (pin "3") (pinfunction "D_3") (pintype "passive"))
      (node (ref "R12") (pin "1") (pinfunction "1_1") (pintype "passive"))
      (node (ref "R16") (pin "1") (pinfunction "1_1") (pintype "passive"))
      (node (ref "U4") (pin "44") (pinfunction "(SDA/INT1)PD1_44") (pintype "bidirectional"))
    )
    (net (code "49") (name "/TXLED") (class "Default")
      (node (ref "TX") (pin "C") (pinfunction "C_C") (pintype "passive"))
      (node (ref "U7") (pin "23") (pinfunction "TXLED_23") (pintype "input"))
    )
    (net (code "50") (name "/USRF_AN") (class "Default")
      (node (ref "U4") (pin "94") (pinfunction "(ADC3)PF3_94") (pintype "bidirectional"))
      (node (ref "USRF") (pin "2") (pinfunction "2_2") (pintype "passive"))
    )
    (net (code "51") (name "/USRF_ON") (class "Default")
      (node (ref "U4") (pin "51") (pinfunction "(WR)PG0_51") (pintype "bidirectional"))
      (node (ref "USRF") (pin "1") (pinfunction "1_1") (pintype "passive"))
    )
    (net (code "52") (name "/VBATT") (class "Default")
      (node (ref "+") (pin "P$1") (pinfunction "P$1_P$1") (pintype "bidirectional"))
      (node (ref "U$3") (pin "P$1") (pinfunction "P$1_P$1") (pintype "bidirectional"))
      (node (ref "U$4") (pin "P$1") (pinfunction "P$1_P$1") (pintype "bidirectional"))
      (node (ref "V+") (pin "P$1") (pinfunction "P$1_P$1") (pintype "bidirectional"))
    )
    (net (code "53") (name "/XB_RX") (class "Default")
      (node (ref "Q1") (pin "3") (pinfunction "D_3") (pintype "passive"))
      (node (ref "R6") (pin "1") (pinfunction "1_1") (pintype "passive"))
      (node (ref "U4") (pin "45") (pinfunction "(RXD1/INT2)PD2_45") (pintype "bidirectional"))
    )
    (net (code "54") (name "/XB_TX") (class "Default")
      (node (ref "Q2") (pin "3") (pinfunction "D_3") (pintype "passive"))
      (node (ref "R7") (pin "1") (pinfunction "1_1") (pintype "passive"))
      (node (ref "U4") (pin "46") (pinfunction "(TXD1/INT3)PD3_46") (pintype "bidirectional"))
    )
    (net (code "55") (name "/XTAL1") (class "Default")
      (node (ref "CSTCE16MOV53-RO16MHZ") (pin "3") (pinfunction "3_3") (pintype "passive"))
      (node (ref "R8") (pin "1") (pinfunction "1_1") (pintype "passive"))
      (node (ref "U4") (pin "34") (pinfunction "XTAL1_34") (pintype "input"))
    )
    (net (code "56") (name "/XTAL2") (class "Default")
      (node (ref "CSTCE16MOV53-RO16MHZ") (pin "1") (pinfunction "1_1") (pintype "passive"))
      (node (ref "R8") (pin "2") (pinfunction "2_2") (pintype "passive"))
      (node (ref "U4") (pin "33") (pinfunction "XTAL2_33") (pintype "output"))
    )
    (net (code "57") (name "1.8V") (class "Default")
      (node (ref "1.8VREG") (pin "5") (pinfunction "OUT_5") (pintype "passive"))
      (node (ref "C7") (pin "1") (pinfunction "1_1") (pintype "passive"))
      (node (ref "Q3") (pin "1") (pinfunction "G_1") (pintype "passive"))
      (node (ref "Q4") (pin "1") (pinfunction "G_1") (pintype "passive"))
      (node (ref "R10") (pin "2") (pinfunction "2_2") (pintype "passive"))
      (node (ref "R11") (pin "2") (pinfunction "2_2") (pintype "passive"))
      (node (ref "U3") (pin "21") (pinfunction "VDD_M_21") (pintype "bidirectional"))
      (node (ref "U3") (pin "22") (pinfunction "VDD_IO_22") (pintype "bidirectional"))
      (node (ref "U3") (pin "23") (pinfunction "VDD_IO_23") (pintype "bidirectional"))
      (node (ref "U3") (pin "5") (pinfunction "VDD_I2C_5") (pintype "bidirectional"))
    )
    (net (code "58") (name "GND") (class "Default")
      (node (ref "1.8VREG") (pin "2") (pinfunction "GND_2") (pintype "input"))
      (node (ref "BMP1") (pin "1") (pinfunction "GND_1") (pintype "power_in"))
      (node (ref "C1") (pin "2") (pinfunction "2_2") (pintype "passive"))
      (node (ref "C10") (pin "2") (pinfunction "2_2") (pintype "passive"))
      (node (ref "C12") (pin "C") (pinfunction "-_C") (pintype "passive"))
      (node (ref "C13") (pin "C") (pinfunction "-_C") (pintype "passive"))
      (node (ref "C14") (pin "2") (pinfunction "2_2") (pintype "passive"))
      (node (ref "C16") (pin "2") (pinfunction "2_2") (pintype "passive"))
      (node (ref "C17") (pin "2") (pinfunction "2_2") (pintype "passive"))
      (node (ref "C18") (pin "C") (pinfunction "-_C") (pintype "passive"))
      (node (ref "C2") (pin "2") (pinfunction "2_2") (pintype "passive"))
      (node (ref "C3") (pin "2") (pinfunction "2_2") (pintype "passive"))
      (node (ref "C4") (pin "2") (pinfunction "2_2") (pintype "passive"))
      (node (ref "C5") (pin "2") (pinfunction "2_2") (pintype "passive"))
      (node (ref "C6") (pin "2") (pinfunction "2_2") (pintype "passive"))
      (node (ref "C7") (pin "2") (pinfunction "2_2") (pintype "passive"))
      (node (ref "C8") (pin "2") (pinfunction "2_2") (pintype "passive"))
      (node (ref "C9") (pin "2") (pinfunction "2_2") (pintype "passive"))
      (node (ref "CSTCE16MOV53-RO16MHZ") (pin "2") (pinfunction "2_2") (pintype "passive"))
      (node (ref "DIO1") (pin "C") (pinfunction "C_C") (pintype "passive"))
      (node (ref "ICSP") (pin "10") (pinfunction "10_10") (pintype "passive"))
      (node (ref "ICSP") (pin "4") (pinfunction "4_4") (pintype "passive"))
      (node (ref "ICSP") (pin "6") (pinfunction "6_6") (pintype "passive"))
      (node (ref "ICSP") (pin "8") (pinfunction "8_8") (pintype "passive"))
      (node (ref "JP1") (pin "GND$1") (pinfunction "GND$1_GND$1") (pintype "bidirectional"))
      (node (ref "JP1") (pin "GND$2") (pinfunction "GND$2_GND$2") (pintype "bidirectional"))
      (node (ref "JP1") (pin "P$4") (pinfunction "P$4_P$4") (pintype "bidirectional"))
      (node (ref "M1") (pin "1") (pinfunction "1_1") (pintype "passive"))
      (node (ref "M2") (pin "1") (pinfunction "1_1") (pintype "passive"))
      (node (ref "M3") (pin "1") (pinfunction "1_1") (pintype "passive"))
      (node (ref "M4") (pin "1") (pinfunction "1_1") (pintype "passive"))
      (node (ref "PT1") (pin "P$1") (pinfunction "P$1_P$1") (pintype "bidirectional"))
      (node (ref "PT2") (pin "P$1") (pinfunction "P$1_P$1") (pintype "bidirectional"))
      (node (ref "PT3") (pin "P$1") (pinfunction "P$1_P$1") (pintype "bidirectional"))
      (node (ref "R13") (pin "1") (pinfunction "1_1") (pintype "passive"))
      (node (ref "R17") (pin "1") (pinfunction "1_1") (pintype "passive"))
      (node (ref "R20") (pin "2") (pinfunction "2_2") (pintype "passive"))
      (node (ref "R22") (pin "1") (pinfunction "1_1") (pintype "passive"))
      (node (ref "R24") (pin "2") (pinfunction "2_2") (pintype "passive"))
      (node (ref "REG1") (pin "1") (pinfunction "GND_1") (pintype "bidirectional"))
      (node (ref "RSSI") (pin "C") (pinfunction "C_C") (pintype "passive"))
      (node (ref "RST") (pin "P$2") (pinfunction "2_P$2") (pintype "passive"))
      (node (ref "U$1") (pin "4") (pinfunction "GND$1_4") (pintype "bidirectional"))
      (node (ref "U$1") (pin "5") (pinfunction "GND$2_5") (pintype "bidirectional"))
      (node (ref "U$2") (pin "10") (pinfunction "GND_10") (pintype "power_in"))
      (node (ref "U1") (pin "6") (pinfunction "GND_6") (pintype "bidirectional"))
      (node (ref "U1") (pin "CD1") (pinfunction "SHIELD_CD1") (pintype "bidirectional"))
      (node (ref "U1") (pin "CD2") (pinfunction "SHIELD_CD2") (pintype "bidirectional"))
      (node (ref "U1") (pin "GND1") (pinfunction "SHIELD_GND1") (pintype "bidirectional"))
      (node (ref "U1") (pin "GND3") (pinfunction "SHIELD_GND3") (pintype "bidirectional"))
      (node (ref "U2") (pin "8") (pinfunction "GND_8") (pintype "bidirectional"))
      (node (ref "U3") (pin "1") (pinfunction "GND_1") (pintype "bidirectional"))
      (node (ref "U3") (pin "17") (pinfunction "GND_17") (pintype "bidirectional"))
      (node (ref "U3") (pin "2") (pinfunction "GND_2") (pintype "bidirectional"))
      (node (ref "U3") (pin "28") (pinfunction "GND_28") (pintype "bidirectional"))
      (node (ref "U3") (pin "3") (pinfunction "GND_3") (pintype "bidirectional"))
      (node (ref "U3") (pin "4") (pinfunction "SA0_A_4") (pintype "bidirectional"))
      (node (ref "U4") (pin "11") (pinfunction "GND_11") (pintype "power_in"))
      (node (ref "U4") (pin "32") (pinfunction "GND1_32") (pintype "power_in"))
      (node (ref "U4") (pin "62") (pinfunction "GND2_62") (pintype "power_in"))
      (node (ref "U4") (pin "81") (pinfunction "GND3_81") (pintype "power_in"))
      (node (ref "U4") (pin "99") (pinfunction "AGND_99") (pintype "power_in"))
      (node (ref "U5") (pin "10") (pinfunction "RSVDG_10") (pintype "bidirectional"))
      (node (ref "U5") (pin "11") (pinfunction "RSDVG_11") (pintype "bidirectional"))
      (node (ref "U5") (pin "12") (pinfunction "RSVDG_12") (pintype "bidirectional"))
      (node (ref "U5") (pin "13") (pinfunction "GND_13") (pintype "bidirectional"))
      (node (ref "U5") (pin "8") (pinfunction "RSVDG_8") (pintype "bidirectional"))
      (node (ref "U5") (pin "9") (pinfunction "RSVDG_9") (pintype "bidirectional"))
      (node (ref "U7") (pin "18") (pinfunction "GND18_18") (pintype "power_in"))
      (node (ref "U7") (pin "21") (pinfunction "GND21_21") (pintype "power_in"))
      (node (ref "U7") (pin "25") (pinfunction "AGND_25") (pintype "power_in"))
      (node (ref "U7") (pin "26") (pinfunction "TEST_26") (pintype "input"))
      (node (ref "U7") (pin "7") (pinfunction "GND7_7") (pintype "power_in"))
      (node (ref "USRF") (pin "3") (pinfunction "3_3") (pintype "passive"))
      (node (ref "X2") (pin "GND") (pinfunction "GND_GND") (pintype "bidirectional"))
    )
    (net (code "59") (name "Net-(1.8VREG-BP)") (class "Default")
      (node (ref "1.8VREG") (pin "4") (pinfunction "BP_4") (pintype "input"))
      (node (ref "C9") (pin "1") (pinfunction "1_1") (pintype "passive"))
    )
    (net (code "60") (name "Net-(5_PWR-PadC)") (class "Default")
      (node (ref "5_PWR") (pin "C") (pinfunction "C_C") (pintype "passive"))
      (node (ref "R13") (pin "2") (pinfunction "2_2") (pintype "passive"))
    )
    (net (code "61") (name "Net-(C15-Pad2)") (class "Default")
      (node (ref "C15") (pin "2") (pinfunction "2_2") (pintype "passive"))
      (node (ref "R24") (pin "1") (pinfunction "1_1") (pintype "passive"))
    )
    (net (code "62") (name "Net-(D2-C)") (class "Default")
      (node (ref "D2") (pin "2") (pinfunction "C_2") (pintype "passive"))
      (node (ref "F1") (pin "1") (pinfunction "1_1") (pintype "passive"))
    )
    (net (code "63") (name "Net-(DIO1-PadA)") (class "Default")
      (node (ref "DIO1") (pin "A") (pinfunction "A_A") (pintype "passive"))
      (node (ref "R1") (pin "2") (pinfunction "2_2") (pintype "passive"))
    )
    (net (code "64") (name "Net-(HB-PadC)") (class "Default")
      (node (ref "HB") (pin "C") (pinfunction "C_C") (pintype "passive"))
      (node (ref "R17") (pin "2") (pinfunction "2_2") (pintype "passive"))
    )
    (net (code "65") (name "Net-(JP1-PadP$1)") (class "Default")
      (node (ref "JP1") (pin "P$1") (pinfunction "P$1_P$1") (pintype "bidirectional"))
      (node (ref "R15") (pin "2") (pinfunction "2_2") (pintype "passive"))
    )
    (net (code "66") (name "Net-(JP1-PadP$2)") (class "Default")
      (node (ref "JP1") (pin "P$2") (pinfunction "P$2_P$2") (pintype "bidirectional"))
      (node (ref "R18") (pin "2") (pinfunction "2_2") (pintype "passive"))
    )
    (net (code "67") (name "Net-(Q3-S)") (class "Default")
      (node (ref "Q3") (pin "2") (pinfunction "S_2") (pintype "passive"))
      (node (ref "R11") (pin "1") (pinfunction "1_1") (pintype "passive"))
      (node (ref "U3") (pin "20") (pinfunction "SCL_M_20") (pintype "bidirectional"))
      (node (ref "U3") (pin "24") (pinfunction "SCL_A_24") (pintype "bidirectional"))
    )
    (net (code "68") (name "Net-(Q4-S)") (class "Default")
      (node (ref "Q4") (pin "2") (pinfunction "S_2") (pintype "passive"))
      (node (ref "R10") (pin "1") (pinfunction "1_1") (pintype "passive"))
      (node (ref "U3") (pin "19") (pinfunction "SDA_M_19") (pintype "bidirectional"))
      (node (ref "U3") (pin "25") (pinfunction "SDA_A_25") (pintype "bidirectional"))
    )
    (net (code "69") (name "Net-(R2-Pad2)") (class "Default")
      (node (ref "R2") (pin "2") (pinfunction "2_2") (pintype "passive"))
      (node (ref "RSSI") (pin "A") (pinfunction "A_A") (pintype "passive"))
    )
    (net (code "70") (name "Net-(R19-Pad1)") (class "Default")
      (node (ref "R19") (pin "1") (pinfunction "1_1") (pintype "passive"))
      (node (ref "R22") (pin "2") (pinfunction "2_2") (pintype "passive"))
    )
    (net (code "71") (name "Net-(R25-Pad1)") (class "Default")
      (node (ref "R25") (pin "1") (pinfunction "1_1") (pintype "passive"))
      (node (ref "TX") (pin "A") (pinfunction "A_A") (pintype "passive"))
    )
    (net (code "72") (name "Net-(R26-Pad1)") (class "Default")
      (node (ref "R26") (pin "1") (pinfunction "1_1") (pintype "passive"))
      (node (ref "RX") (pin "A") (pinfunction "A_A") (pintype "passive"))
    )
    (net (code "73") (name "Net-(U1-CS)") (class "Default")
      (node (ref "U1") (pin "2") (pinfunction "CS_2") (pintype "bidirectional"))
      (node (ref "U2") (pin "2") (pinfunction "1Y_2") (pintype "bidirectional"))
    )
    (net (code "74") (name "Net-(U1-DI)") (class "Default")
      (node (ref "U1") (pin "3") (pinfunction "DI_3") (pintype "bidirectional"))
      (node (ref "U2") (pin "4") (pinfunction "2Y_4") (pintype "bidirectional"))
    )
    (net (code "75") (name "Net-(U1-SCK)") (class "Default")
      (node (ref "U1") (pin "5") (pinfunction "SCK_5") (pintype "bidirectional"))
      (node (ref "U2") (pin "6") (pinfunction "3Y_6") (pintype "bidirectional"))
    )
    (net (code "76") (name "Net-(U3-C1)") (class "Default")
      (node (ref "C10") (pin "1") (pinfunction "1_1") (pintype "passive"))
      (node (ref "U3") (pin "15") (pinfunction "C1_15") (pintype "bidirectional"))
    )
    (net (code "77") (name "Net-(U3-SET1)") (class "Default")
      (node (ref "C11") (pin "1") (pinfunction "1_1") (pintype "passive"))
      (node (ref "U3") (pin "16") (pinfunction "SET1_16") (pintype "bidirectional"))
    )
    (net (code "78") (name "Net-(U3-SET2)") (class "Default")
      (node (ref "C11") (pin "2") (pinfunction "2_2") (pintype "passive"))
      (node (ref "U3") (pin "12") (pinfunction "SET2_12") (pintype "bidirectional"))
    )
    (net (code "79") (name "Net-(U5-PLL)") (class "Default")
      (node (ref "C15") (pin "1") (pinfunction "1_1") (pintype "passive"))
      (node (ref "C16") (pin "1") (pinfunction "1_1") (pintype "passive"))
      (node (ref "U5") (pin "14") (pinfunction "PLL_14") (pintype "bidirectional"))
    )
    (net (code "80") (name "Net-(U7-USBDM)") (class "Default")
      (node (ref "U7") (pin "16") (pinfunction "USBDM_16") (pintype "bidirectional"))
      (node (ref "X2") (pin "D-") (pinfunction "D-_D-") (pintype "bidirectional"))
    )
    (net (code "81") (name "Net-(U7-USBDP)") (class "Default")
      (node (ref "U7") (pin "15") (pinfunction "USBDP_15") (pintype "bidirectional"))
      (node (ref "X2") (pin "D+") (pinfunction "D+_D+") (pintype "bidirectional"))
    )
    (net (code "82") (name "unconnected-(BMP1-EOC-Pad2)") (class "Default")
      (node (ref "BMP1") (pin "2") (pinfunction "EOC_2") (pintype "output"))
    )
    (net (code "83") (name "unconnected-(BMP1-NC-Pad5)") (class "Default")
      (node (ref "BMP1") (pin "5") (pinfunction "NC_5") (pintype "bidirectional"))
    )
    (net (code "84") (name "unconnected-(BMP1-XCLR-Pad8)") (class "Default")
      (node (ref "BMP1") (pin "8") (pinfunction "XCLR_8") (pintype "input"))
    )
    (net (code "85") (name "unconnected-(ICSP-Pad3)") (class "Default")
      (node (ref "ICSP") (pin "3") (pinfunction "3_3") (pintype "passive"))
    )
    (net (code "86") (name "unconnected-(SEL1-Pad3)") (class "Default")
      (node (ref "SEL1") (pin "3") (pinfunction "3_3") (pintype "passive"))
    )
    (net (code "87") (name "unconnected-(SEL2-Pad3)") (class "Default")
      (node (ref "SEL2") (pin "3") (pinfunction "3_3") (pintype "passive"))
    )
    (net (code "88") (name "unconnected-(SEL3-Pad3)") (class "Default")
      (node (ref "SEL3") (pin "3") (pinfunction "3_3") (pintype "passive"))
    )
    (net (code "89") (name "unconnected-(SEL4-Pad3)") (class "Default")
      (node (ref "SEL4") (pin "3") (pinfunction "3_3") (pintype "passive"))
    )
    (net (code "90") (name "unconnected-(U$2-CTS-Pad12)") (class "Default")
      (node (ref "U$2") (pin "12") (pinfunction "CTS_12") (pintype "output"))
    )
    (net (code "91") (name "unconnected-(U$2-DTR-Pad9)") (class "Default")
      (node (ref "U$2") (pin "9") (pinfunction "DTR_9") (pintype "bidirectional"))
    )
    (net (code "92") (name "unconnected-(U$2-RESET-Pad5)") (class "Default")
      (node (ref "U$2") (pin "5") (pinfunction "RESET_5") (pintype "input"))
    )
    (net (code "93") (name "unconnected-(U$2-RTS-Pad16)") (class "Default")
      (node (ref "U$2") (pin "16") (pinfunction "RTS_16") (pintype "input"))
    )
    (net (code "94") (name "unconnected-(U1-NC-Pad1)") (class "Default")
      (node (ref "U1") (pin "1") (pinfunction "NC_1") (pintype "bidirectional"))
    )
    (net (code "95") (name "unconnected-(U1-RSV-Pad8)") (class "Default")
      (node (ref "U1") (pin "8") (pinfunction "RSV_8") (pintype "bidirectional"))
    )
    (net (code "96") (name "unconnected-(U2-4A-Pad9)") (class "Default")
      (node (ref "U2") (pin "9") (pinfunction "4A_9") (pintype "bidirectional"))
    )
    (net (code "97") (name "unconnected-(U2-4Y-Pad10)") (class "Default")
      (node (ref "U2") (pin "10") (pinfunction "4Y_10") (pintype "bidirectional"))
    )
    (net (code "98") (name "unconnected-(U2-5A-Pad11)") (class "Default")
      (node (ref "U2") (pin "11") (pinfunction "5A_11") (pintype "bidirectional"))
    )
    (net (code "99") (name "unconnected-(U2-5Y-Pad12)") (class "Default")
      (node (ref "U2") (pin "12") (pinfunction "5Y_12") (pintype "bidirectional"))
    )
    (net (code "100") (name "unconnected-(U2-6A-Pad14)") (class "Default")
      (node (ref "U2") (pin "14") (pinfunction "6A_14") (pintype "bidirectional"))
    )
    (net (code "101") (name "unconnected-(U2-6Y-Pad15)") (class "Default")
      (node (ref "U2") (pin "15") (pinfunction "6Y_15") (pintype "bidirectional"))
    )
    (net (code "102") (name "unconnected-(U3-DRDY_M-Pad18)") (class "Default")
      (node (ref "U3") (pin "18") (pinfunction "DRDY_M_18") (pintype "bidirectional"))
    )
    (net (code "103") (name "unconnected-(U3-INT1-Pad26)") (class "Default")
      (node (ref "U3") (pin "26") (pinfunction "INT1_26") (pintype "bidirectional"))
    )
    (net (code "104") (name "unconnected-(U3-INT2-Pad27)") (class "Default")
      (node (ref "U3") (pin "27") (pinfunction "INT2_27") (pintype "bidirectional"))
    )
    (net (code "105") (name "unconnected-(U4-(A8)PC0-Pad53)") (class "Default")
      (node (ref "U4") (pin "53") (pinfunction "(A8)PC0_53") (pintype "bidirectional"))
    )
    (net (code "106") (name "unconnected-(U4-(A9)PC1-Pad54)") (class "Default")
      (node (ref "U4") (pin "54") (pinfunction "(A9)PC1_54") (pintype "bidirectional"))
    )
    (net (code "107") (name "unconnected-(U4-(A10)PC2-Pad55)") (class "Default")
      (node (ref "U4") (pin "55") (pinfunction "(A10)PC2_55") (pintype "bidirectional"))
    )
    (net (code "108") (name "unconnected-(U4-(A11)PC3-Pad56)") (class "Default")
      (node (ref "U4") (pin "56") (pinfunction "(A11)PC3_56") (pintype "bidirectional"))
    )
    (net (code "109") (name "unconnected-(U4-(A12)PC4-Pad57)") (class "Default")
      (node (ref "U4") (pin "57") (pinfunction "(A12)PC4_57") (pintype "bidirectional"))
    )
    (net (code "110") (name "unconnected-(U4-(A13)PC5-Pad58)") (class "Default")
      (node (ref "U4") (pin "58") (pinfunction "(A13)PC5_58") (pintype "bidirectional"))
    )
    (net (code "111") (name "unconnected-(U4-(A14)PC6-Pad59)") (class "Default")
      (node (ref "U4") (pin "59") (pinfunction "(A14)PC6_59") (pintype "bidirectional"))
    )
    (net (code "112") (name "unconnected-(U4-(A15)PC7-Pad60)") (class "Default")
      (node (ref "U4") (pin "60") (pinfunction "(A15)PC7_60") (pintype "bidirectional"))
    )
    (net (code "113") (name "unconnected-(U4-(AD0)PA0-Pad78)") (class "Default")
      (node (ref "U4") (pin "78") (pinfunction "(AD0)PA0_78") (pintype "bidirectional"))
    )
    (net (code "114") (name "unconnected-(U4-(AD1)PA1-Pad77)") (class "Default")
      (node (ref "U4") (pin "77") (pinfunction "(AD1)PA1_77") (pintype "bidirectional"))
    )
    (net (code "115") (name "unconnected-(U4-(AD2)PA2-Pad76)") (class "Default")
      (node (ref "U4") (pin "76") (pinfunction "(AD2)PA2_76") (pintype "bidirectional"))
    )
    (net (code "116") (name "unconnected-(U4-(AD3)PA3-Pad75)") (class "Default")
      (node (ref "U4") (pin "75") (pinfunction "(AD3)PA3_75") (pintype "bidirectional"))
    )
    (net (code "117") (name "unconnected-(U4-(AD4)PA4-Pad74)") (class "Default")
      (node (ref "U4") (pin "74") (pinfunction "(AD4)PA4_74") (pintype "bidirectional"))
    )
    (net (code "118") (name "unconnected-(U4-(AD5)PA5-Pad73)") (class "Default")
      (node (ref "U4") (pin "73") (pinfunction "(AD5)PA5_73") (pintype "bidirectional"))
    )
    (net (code "119") (name "unconnected-(U4-(AD6)PA6-Pad72)") (class "Default")
      (node (ref "U4") (pin "72") (pinfunction "(AD6)PA6_72") (pintype "bidirectional"))
    )
    (net (code "120") (name "unconnected-(U4-(AD7)PA7-Pad71)") (class "Default")
      (node (ref "U4") (pin "71") (pinfunction "(AD7)PA7_71") (pintype "bidirectional"))
    )
    (net (code "121") (name "unconnected-(U4-(ADC4{slash}TCK)PF4-Pad93)") (class "Default")
      (node (ref "U4") (pin "93") (pinfunction "(ADC4/TCK)PF4_93") (pintype "bidirectional"))
    )
    (net (code "122") (name "unconnected-(U4-(ADC5{slash}TMS)PF5-Pad92)") (class "Default")
      (node (ref "U4") (pin "92") (pinfunction "(ADC5/TMS)PF5_92") (pintype "bidirectional"))
    )
    (net (code "123") (name "unconnected-(U4-(ADC6{slash}TDO)PF6-Pad91)") (class "Default")
      (node (ref "U4") (pin "91") (pinfunction "(ADC6/TDO)PF6_91") (pintype "bidirectional"))
    )
    (net (code "124") (name "unconnected-(U4-(ADC7{slash}TDI)PF7-Pad90)") (class "Default")
      (node (ref "U4") (pin "90") (pinfunction "(ADC7/TDI)PF7_90") (pintype "bidirectional"))
    )
    (net (code "125") (name "unconnected-(U4-(ALE)PG2-Pad70)") (class "Default")
      (node (ref "U4") (pin "70") (pinfunction "(ALE)PG2_70") (pintype "bidirectional"))
    )
    (net (code "126") (name "unconnected-(U4-(CLKO{slash}ICP3{slash}INT7)PE7-Pad9)") (class "Default")
      (node (ref "U4") (pin "9") (pinfunction "(CLKO/ICP3/INT7)PE7_9") (pintype "bidirectional"))
    )
    (net (code "127") (name "unconnected-(U4-(ICP1)PD4-Pad47)") (class "Default")
      (node (ref "U4") (pin "47") (pinfunction "(ICP1)PD4_47") (pintype "bidirectional"))
    )
    (net (code "128") (name "unconnected-(U4-(OC0A{slash}OC1C{slash}PCINT7)PB7-Pad26)") (class "Default")
      (node (ref "U4") (pin "26") (pinfunction "(OC0A/OC1C/PCINT7)PB7_26") (pintype "bidirectional"))
    )
    (net (code "129") (name "unconnected-(U4-(OC0B)PG5-Pad1)") (class "Default")
      (node (ref "U4") (pin "1") (pinfunction "(OC0B)PG5_1") (pintype "bidirectional"))
    )
    (net (code "130") (name "unconnected-(U4-(OC1A{slash}PCINT5)PB5-Pad24)") (class "Default")
      (node (ref "U4") (pin "24") (pinfunction "(OC1A/PCINT5)PB5_24") (pintype "bidirectional"))
    )
    (net (code "131") (name "unconnected-(U4-(OC1B{slash}PCINT6)PB6-Pad25)") (class "Default")
      (node (ref "U4") (pin "25") (pinfunction "(OC1B/PCINT6)PB6_25") (pintype "bidirectional"))
    )
    (net (code "132") (name "unconnected-(U4-(OC2A{slash}PCINT4)PB4-Pad23)") (class "Default")
      (node (ref "U4") (pin "23") (pinfunction "(OC2A/PCINT4)PB4_23") (pintype "bidirectional"))
    )
    (net (code "133") (name "unconnected-(U4-(RD)PG1-Pad52)") (class "Default")
      (node (ref "U4") (pin "52") (pinfunction "(RD)PG1_52") (pintype "bidirectional"))
    )
    (net (code "134") (name "unconnected-(U4-(T0)PD7-Pad50)") (class "Default")
      (node (ref "U4") (pin "50") (pinfunction "(T0)PD7_50") (pintype "bidirectional"))
    )
    (net (code "135") (name "unconnected-(U4-(T1)PD6-Pad49)") (class "Default")
      (node (ref "U4") (pin "49") (pinfunction "(T1)PD6_49") (pintype "bidirectional"))
    )
    (net (code "136") (name "unconnected-(U4-(T3{slash}INT6)PE6-Pad8)") (class "Default")
      (node (ref "U4") (pin "8") (pinfunction "(T3/INT6)PE6_8") (pintype "bidirectional"))
    )
    (net (code "137") (name "unconnected-(U4-(TOSC1)PG4-Pad29)") (class "Default")
      (node (ref "U4") (pin "29") (pinfunction "(TOSC1)PG4_29") (pintype "bidirectional"))
    )
    (net (code "138") (name "unconnected-(U4-(TOSC2)PG3-Pad28)") (class "Default")
      (node (ref "U4") (pin "28") (pinfunction "(TOSC2)PG3_28") (pintype "bidirectional"))
    )
    (net (code "139") (name "unconnected-(U4-(XCK0{slash}AIN0)PE2-Pad4)") (class "Default")
      (node (ref "U4") (pin "4") (pinfunction "(XCK0/AIN0)PE2_4") (pintype "bidirectional"))
    )
    (net (code "140") (name "unconnected-(U4-(XCK1)PD5-Pad48)") (class "Default")
      (node (ref "U4") (pin "48") (pinfunction "(XCK1)PD5_48") (pintype "bidirectional"))
    )
    (net (code "141") (name "unconnected-(U4-PH0(RXD2)-Pad12)") (class "Default")
      (node (ref "U4") (pin "12") (pinfunction "PH0(RXD2)_12") (pintype "bidirectional"))
    )
    (net (code "142") (name "unconnected-(U4-PH1(TXD2)-Pad13)") (class "Default")
      (node (ref "U4") (pin "13") (pinfunction "PH1(TXD2)_13") (pintype "bidirectional"))
    )
    (net (code "143") (name "unconnected-(U4-PH2(XCK2)-Pad14)") (class "Default")
      (node (ref "U4") (pin "14") (pinfunction "PH2(XCK2)_14") (pintype "bidirectional"))
    )
    (net (code "144") (name "unconnected-(U4-PH7(T4)-Pad27)") (class "Default")
      (node (ref "U4") (pin "27") (pinfunction "PH7(T4)_27") (pintype "bidirectional"))
    )
    (net (code "145") (name "unconnected-(U4-PJ0(RXD3{slash}PCINT9)-Pad63)") (class "Default")
      (node (ref "U4") (pin "63") (pinfunction "PJ0(RXD3/PCINT9)_63") (pintype "bidirectional"))
    )
    (net (code "146") (name "unconnected-(U4-PJ1(TXD3{slash}PCINT10)-Pad64)") (class "Default")
      (node (ref "U4") (pin "64") (pinfunction "PJ1(TXD3/PCINT10)_64") (pintype "bidirectional"))
    )
    (net (code "147") (name "unconnected-(U4-PJ2(XCK3{slash}PCINT11)-Pad65)") (class "Default")
      (node (ref "U4") (pin "65") (pinfunction "PJ2(XCK3/PCINT11)_65") (pintype "bidirectional"))
    )
    (net (code "148") (name "unconnected-(U4-PJ3(PCINT12)-Pad66)") (class "Default")
      (node (ref "U4") (pin "66") (pinfunction "PJ3(PCINT12)_66") (pintype "bidirectional"))
    )
    (net (code "149") (name "unconnected-(U4-PJ4(PCINT13)-Pad67)") (class "Default")
      (node (ref "U4") (pin "67") (pinfunction "PJ4(PCINT13)_67") (pintype "bidirectional"))
    )
    (net (code "150") (name "unconnected-(U4-PJ5(PCINT14)-Pad68)") (class "Default")
      (node (ref "U4") (pin "68") (pinfunction "PJ5(PCINT14)_68") (pintype "bidirectional"))
    )
    (net (code "151") (name "unconnected-(U4-PJ6(PCINT15)-Pad69)") (class "Default")
      (node (ref "U4") (pin "69") (pinfunction "PJ6(PCINT15)_69") (pintype "bidirectional"))
    )
    (net (code "152") (name "unconnected-(U4-PJ7-Pad79)") (class "Default")
      (node (ref "U4") (pin "79") (pinfunction "PJ7_79") (pintype "bidirectional"))
    )
    (net (code "153") (name "unconnected-(U4-PK0(ADC8{slash}PCINT16)-Pad89)") (class "Default")
      (node (ref "U4") (pin "89") (pinfunction "PK0(ADC8/PCINT16)_89") (pintype "bidirectional"))
    )
    (net (code "154") (name "unconnected-(U4-PK1(ADC9{slash}PCINT17)-Pad88)") (class "Default")
      (node (ref "U4") (pin "88") (pinfunction "PK1(ADC9/PCINT17)_88") (pintype "bidirectional"))
    )
    (net (code "155") (name "unconnected-(U4-PK2(ADC10{slash}PCINT18)-Pad87)") (class "Default")
      (node (ref "U4") (pin "87") (pinfunction "PK2(ADC10/PCINT18)_87") (pintype "bidirectional"))
    )
    (net (code "156") (name "unconnected-(U4-PK3(ADC11{slash}PCINT19)-Pad86)") (class "Default")
      (node (ref "U4") (pin "86") (pinfunction "PK3(ADC11/PCINT19)_86") (pintype "bidirectional"))
    )
    (net (code "157") (name "unconnected-(U4-PK4(ADC12{slash}PCINT20)-Pad85)") (class "Default")
      (node (ref "U4") (pin "85") (pinfunction "PK4(ADC12/PCINT20)_85") (pintype "bidirectional"))
    )
    (net (code "158") (name "unconnected-(U4-PK5(ADC13{slash}PCINT21)-Pad84)") (class "Default")
      (node (ref "U4") (pin "84") (pinfunction "PK5(ADC13/PCINT21)_84") (pintype "bidirectional"))
    )
    (net (code "159") (name "unconnected-(U4-PK6(ADC14{slash}PCINT22)-Pad83)") (class "Default")
      (node (ref "U4") (pin "83") (pinfunction "PK6(ADC14/PCINT22)_83") (pintype "bidirectional"))
    )
    (net (code "160") (name "unconnected-(U4-PK7(ADC15{slash}PCINT23)-Pad82)") (class "Default")
      (node (ref "U4") (pin "82") (pinfunction "PK7(ADC15/PCINT23)_82") (pintype "bidirectional"))
    )
    (net (code "161") (name "unconnected-(U4-PL0(ICP4)-Pad35)") (class "Default")
      (node (ref "U4") (pin "35") (pinfunction "PL0(ICP4)_35") (pintype "bidirectional"))
    )
    (net (code "162") (name "unconnected-(U4-PL1(ICP5)-Pad36)") (class "Default")
      (node (ref "U4") (pin "36") (pinfunction "PL1(ICP5)_36") (pintype "bidirectional"))
    )
    (net (code "163") (name "unconnected-(U4-PL2(T5)-Pad37)") (class "Default")
      (node (ref "U4") (pin "37") (pinfunction "PL2(T5)_37") (pintype "bidirectional"))
    )
    (net (code "164") (name "unconnected-(U4-PL5(OC5C)-Pad40)") (class "Default")
      (node (ref "U4") (pin "40") (pinfunction "PL5(OC5C)_40") (pintype "bidirectional"))
    )
    (net (code "165") (name "unconnected-(U4-PL6-Pad41)") (class "Default")
      (node (ref "U4") (pin "41") (pinfunction "PL6_41") (pintype "bidirectional"))
    )
    (net (code "166") (name "unconnected-(U4-PL7-Pad42)") (class "Default")
      (node (ref "U4") (pin "42") (pinfunction "PL7_42") (pintype "bidirectional"))
    )
    (net (code "167") (name "unconnected-(U5-INT1-Pad7)") (class "Default")
      (node (ref "U5") (pin "7") (pinfunction "INT1_7") (pintype "bidirectional"))
    )
    (net (code "168") (name "unconnected-(U5-INT2-Pad6)") (class "Default")
      (node (ref "U5") (pin "6") (pinfunction "INT2_6") (pintype "bidirectional"))
    )
    (net (code "169") (name "unconnected-(U7-3V3OUT-Pad17)") (class "Default")
      (node (ref "U7") (pin "17") (pinfunction "3V3OUT_17") (pintype "output"))
    )
    (net (code "170") (name "unconnected-(U7-DCD-Pad10)") (class "Default")
      (node (ref "U7") (pin "10") (pinfunction "DCD_10") (pintype "input"))
    )
    (net (code "171") (name "unconnected-(U7-DSR-Pad9)") (class "Default")
      (node (ref "U7") (pin "9") (pinfunction "DSR_9") (pintype "input"))
    )
    (net (code "172") (name "unconnected-(U7-OSCI-Pad27)") (class "Default")
      (node (ref "U7") (pin "27") (pinfunction "OSCI_27") (pintype "input"))
    )
    (net (code "173") (name "unconnected-(U7-OSCO-Pad28)") (class "Default")
      (node (ref "U7") (pin "28") (pinfunction "OSCO_28") (pintype "output"))
    )
    (net (code "174") (name "unconnected-(U7-PWREN-Pad14)") (class "Default")
      (node (ref "U7") (pin "14") (pinfunction "PWREN_14") (pintype "input"))
    )
    (net (code "175") (name "unconnected-(U7-RESET-Pad19)") (class "Default")
      (node (ref "U7") (pin "19") (pinfunction "RESET_19") (pintype "input"))
    )
    (net (code "176") (name "unconnected-(U7-RI-Pad6)") (class "Default")
      (node (ref "U7") (pin "6") (pinfunction "RI_6") (pintype "input"))
    )
    (net (code "177") (name "unconnected-(U7-SLEEP-Pad12)") (class "Default")
      (node (ref "U7") (pin "12") (pinfunction "SLEEP_12") (pintype "input"))
    )
    (net (code "178") (name "unconnected-(U7-TXDEN-Pad13)") (class "Default")
      (node (ref "U7") (pin "13") (pinfunction "TXDEN_13") (pintype "input"))
    )
  )
)
